# blackfin_f_power.net
KiCad netlist of a schematic drawn in Altium Designer
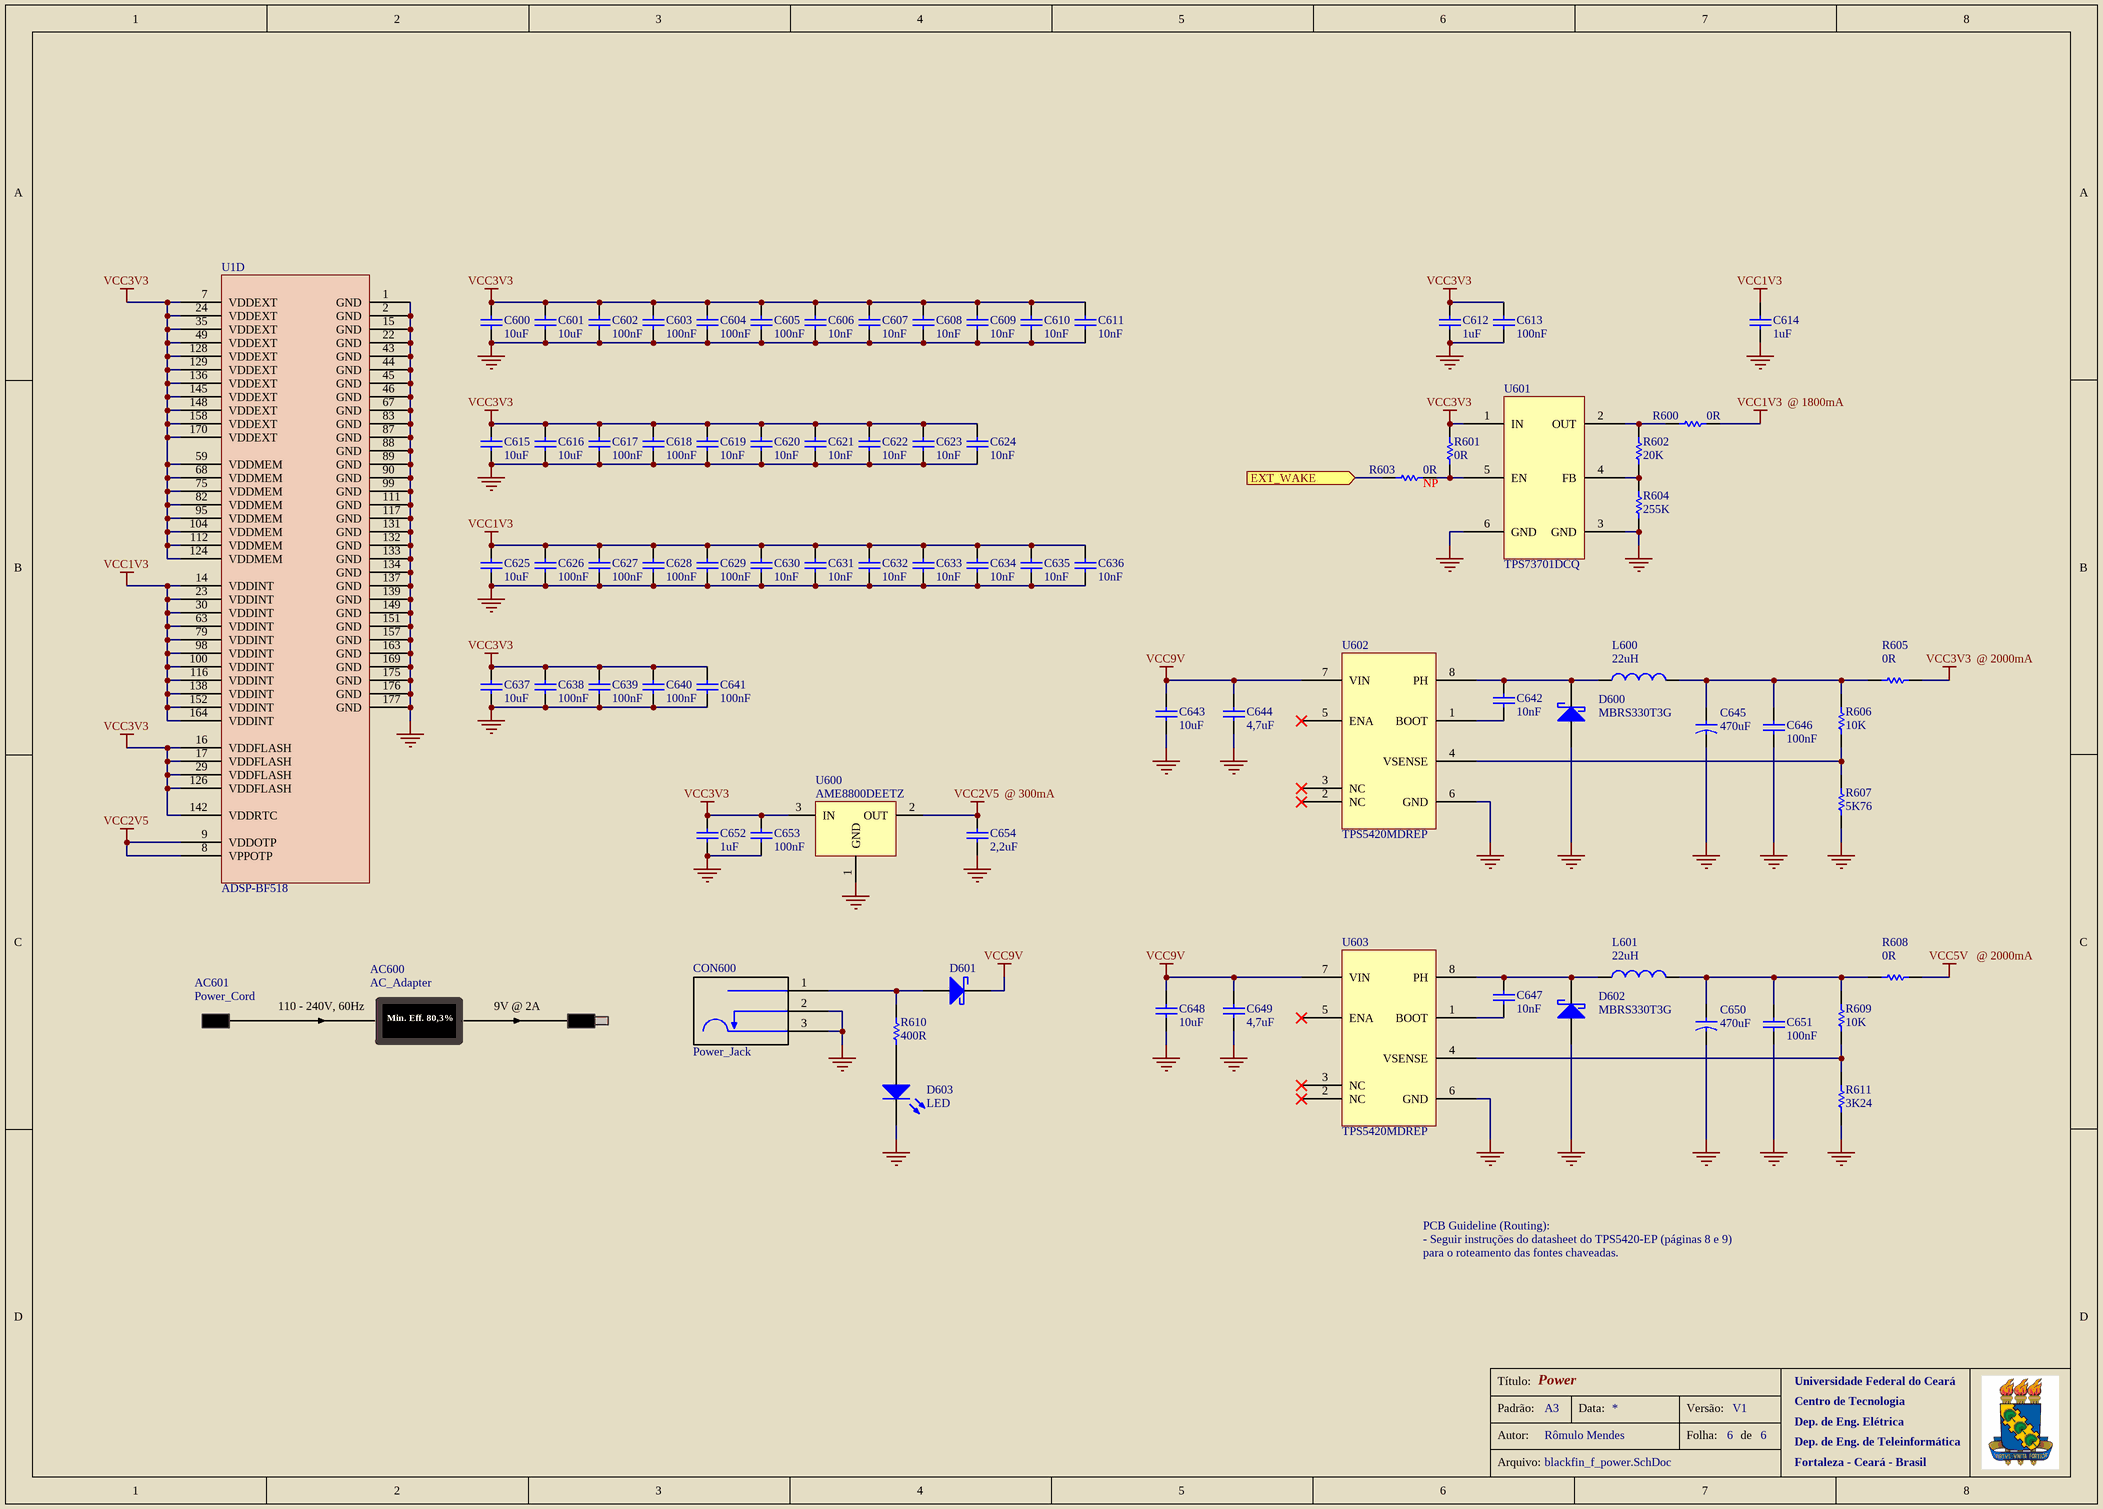
[diagram p0: blackfin_f_power.SchDoc]

(export (version "E")
  (design (tool "Eeschema 10.0.6"))
  (components
    (comp (ref "AC600")
      (value "AC_Adapter")
      (fields
        (field (name "EVENDORPART#") "552-PSA-A18U-090")
        (field (name "PART#") "PSAA18U-090-R")
        (field (name "MANUFACTURER") "Phihong")
      )
      (libsource (lib "blackfin_schlib") (part "AC_Adapter"))
    )
    (comp (ref "AC601")
      (value "Power_Cord")
      (fields
        (field (name "EVENDORPART#") "693-6009.1315")
        (field (name "PART#") "6009.1315")
        (field (name "MANUFACTURER") "Schurter")
      )
      (libsource (lib "blackfin_schlib") (part "Power_Cord"))
    )
    (comp (ref "C600")
      (value "10uF")
      (footprint "blackfin_pcblib:C_0805")
      (fields
        (field (name "EVENDORPART#") "810-C2012Y5V1C106Z")
        (field (name "MANUFACTURER") "TDK")
        (field (name "PART#") "C2012Y5V1C106Z")
      )
      (libsource (lib "blackfin_schlib") (part "Capacitor"))
    )
    (comp (ref "C601")
      (value "10uF")
      (footprint "blackfin_pcblib:C_0805")
      (fields
        (field (name "EVENDORPART#") "810-C2012Y5V1C106Z")
        (field (name "MANUFACTURER") "TDK")
        (field (name "PART#") "C2012Y5V1C106Z")
      )
      (libsource (lib "blackfin_schlib") (part "Capacitor"))
    )
    (comp (ref "C602")
      (value "100nF")
      (footprint "blackfin_pcblib:C_0603")
      (fields
        (field (name "EVENDORPART#") "81-GRM188R71E104KA01")
        (field (name "MANUFACTURER") "Murata")
        (field (name "PART#") "GRM188R71E104KA01J")
      )
      (libsource (lib "blackfin_schlib") (part "Capacitor"))
    )
    (comp (ref "C603")
      (value "100nF")
      (footprint "blackfin_pcblib:C_0603")
      (fields
        (field (name "EVENDORPART#") "81-GRM188R71E104KA01")
        (field (name "MANUFACTURER") "Murata")
        (field (name "PART#") "GRM188R71E104KA01J")
      )
      (libsource (lib "blackfin_schlib") (part "Capacitor"))
    )
    (comp (ref "C604")
      (value "100nF")
      (footprint "blackfin_pcblib:C_0603")
      (fields
        (field (name "EVENDORPART#") "81-GRM188R71E104KA01")
        (field (name "MANUFACTURER") "Murata")
        (field (name "PART#") "GRM188R71E104KA01J")
      )
      (libsource (lib "blackfin_schlib") (part "Capacitor"))
    )
    (comp (ref "C605")
      (value "100nF")
      (footprint "blackfin_pcblib:C_0603")
      (fields
        (field (name "EVENDORPART#") "81-GRM188R71E104KA01")
        (field (name "MANUFACTURER") "Murata")
        (field (name "PART#") "GRM188R71E104KA01J")
      )
      (libsource (lib "blackfin_schlib") (part "Capacitor"))
    )
    (comp (ref "C606")
      (value "10nF")
      (footprint "blackfin_pcblib:C_0603")
      (fields
        (field (name "EVENDORPART#") "77-VJ0603Y103KXAPBC")
        (field (name "MANUFACTURER") "Vishay/Vitramon")
        (field (name "PART#") "VJ0603Y103KXAPW1BC")
      )
      (libsource (lib "blackfin_schlib") (part "Capacitor"))
    )
    (comp (ref "C607")
      (value "10nF")
      (footprint "blackfin_pcblib:C_0603")
      (fields
        (field (name "EVENDORPART#") "77-VJ0603Y103KXAPBC")
        (field (name "MANUFACTURER") "Vishay/Vitramon")
        (field (name "PART#") "VJ0603Y103KXAPW1BC")
      )
      (libsource (lib "blackfin_schlib") (part "Capacitor"))
    )
    (comp (ref "C608")
      (value "10nF")
      (footprint "blackfin_pcblib:C_0603")
      (fields
        (field (name "EVENDORPART#") "77-VJ0603Y103KXAPBC")
        (field (name "MANUFACTURER") "Vishay/Vitramon")
        (field (name "PART#") "VJ0603Y103KXAPW1BC")
      )
      (libsource (lib "blackfin_schlib") (part "Capacitor"))
    )
    (comp (ref "C609")
      (value "10nF")
      (footprint "blackfin_pcblib:C_0603")
      (fields
        (field (name "EVENDORPART#") "77-VJ0603Y103KXAPBC")
        (field (name "MANUFACTURER") "Vishay/Vitramon")
        (field (name "PART#") "VJ0603Y103KXAPW1BC")
      )
      (libsource (lib "blackfin_schlib") (part "Capacitor"))
    )
    (comp (ref "C610")
      (value "10nF")
      (footprint "blackfin_pcblib:C_0603")
      (fields
        (field (name "EVENDORPART#") "77-VJ0603Y103KXAPBC")
        (field (name "MANUFACTURER") "Vishay/Vitramon")
        (field (name "PART#") "VJ0603Y103KXAPW1BC")
      )
      (libsource (lib "blackfin_schlib") (part "Capacitor"))
    )
    (comp (ref "C611")
      (value "10nF")
      (footprint "blackfin_pcblib:C_0603")
      (fields
        (field (name "EVENDORPART#") "77-VJ0603Y103KXAPBC")
        (field (name "MANUFACTURER") "Vishay/Vitramon")
        (field (name "PART#") "VJ0603Y103KXAPW1BC")
      )
      (libsource (lib "blackfin_schlib") (part "Capacitor"))
    )
    (comp (ref "C612")
      (value "1uF")
      (footprint "blackfin_pcblib:C_0603")
      (fields
        (field (name "EVENDORPART#") "81-GRM188F51E105ZA12")
        (field (name "MANUFACTURER") "Murata")
        (field (name "PART#") "GRM188F51E105ZA12D")
      )
      (libsource (lib "blackfin_schlib") (part "Capacitor"))
    )
    (comp (ref "C613")
      (value "100nF")
      (footprint "blackfin_pcblib:C_0603")
      (fields
        (field (name "EVENDORPART#") "81-GRM188R71E104KA01")
        (field (name "MANUFACTURER") "Murata")
        (field (name "PART#") "GRM188R71E104KA01J")
      )
      (libsource (lib "blackfin_schlib") (part "Capacitor"))
    )
    (comp (ref "C614")
      (value "1uF")
      (footprint "blackfin_pcblib:C_0603")
      (fields
        (field (name "EVENDORPART#") "81-GRM188F51E105ZA12")
        (field (name "MANUFACTURER") "Murata")
        (field (name "PART#") "GRM188F51E105ZA12D")
      )
      (libsource (lib "blackfin_schlib") (part "Capacitor"))
    )
    (comp (ref "C615")
      (value "10uF")
      (footprint "blackfin_pcblib:C_0805")
      (fields
        (field (name "EVENDORPART#") "810-C2012Y5V1C106Z")
        (field (name "MANUFACTURER") "TDK")
        (field (name "PART#") "C2012Y5V1C106Z")
      )
      (libsource (lib "blackfin_schlib") (part "Capacitor"))
    )
    (comp (ref "C616")
      (value "10uF")
      (footprint "blackfin_pcblib:C_0805")
      (fields
        (field (name "EVENDORPART#") "810-C2012Y5V1C106Z")
        (field (name "MANUFACTURER") "TDK")
        (field (name "PART#") "C2012Y5V1C106Z")
      )
      (libsource (lib "blackfin_schlib") (part "Capacitor"))
    )
    (comp (ref "C617")
      (value "100nF")
      (footprint "blackfin_pcblib:C_0603")
      (fields
        (field (name "EVENDORPART#") "81-GRM188R71E104KA01")
        (field (name "MANUFACTURER") "Murata")
        (field (name "PART#") "GRM188R71E104KA01J")
      )
      (libsource (lib "blackfin_schlib") (part "Capacitor"))
    )
    (comp (ref "C618")
      (value "100nF")
      (footprint "blackfin_pcblib:C_0603")
      (fields
        (field (name "EVENDORPART#") "81-GRM188R71E104KA01")
        (field (name "MANUFACTURER") "Murata")
        (field (name "PART#") "GRM188R71E104KA01J")
      )
      (libsource (lib "blackfin_schlib") (part "Capacitor"))
    )
    (comp (ref "C619")
      (value "10nF")
      (footprint "blackfin_pcblib:C_0603")
      (fields
        (field (name "EVENDORPART#") "77-VJ0603Y103KXAPBC")
        (field (name "MANUFACTURER") "Vishay/Vitramon")
        (field (name "PART#") "VJ0603Y103KXAPW1BC")
      )
      (libsource (lib "blackfin_schlib") (part "Capacitor"))
    )
    (comp (ref "C620")
      (value "10nF")
      (footprint "blackfin_pcblib:C_0603")
      (fields
        (field (name "EVENDORPART#") "77-VJ0603Y103KXAPBC")
        (field (name "MANUFACTURER") "Vishay/Vitramon")
        (field (name "PART#") "VJ0603Y103KXAPW1BC")
      )
      (libsource (lib "blackfin_schlib") (part "Capacitor"))
    )
    (comp (ref "C621")
      (value "10nF")
      (footprint "blackfin_pcblib:C_0603")
      (fields
        (field (name "EVENDORPART#") "77-VJ0603Y103KXAPBC")
        (field (name "MANUFACTURER") "Vishay/Vitramon")
        (field (name "PART#") "VJ0603Y103KXAPW1BC")
      )
      (libsource (lib "blackfin_schlib") (part "Capacitor"))
    )
    (comp (ref "C622")
      (value "10nF")
      (footprint "blackfin_pcblib:C_0603")
      (fields
        (field (name "EVENDORPART#") "77-VJ0603Y103KXAPBC")
        (field (name "MANUFACTURER") "Vishay/Vitramon")
        (field (name "PART#") "VJ0603Y103KXAPW1BC")
      )
      (libsource (lib "blackfin_schlib") (part "Capacitor"))
    )
    (comp (ref "C623")
      (value "10nF")
      (footprint "blackfin_pcblib:C_0603")
      (fields
        (field (name "EVENDORPART#") "77-VJ0603Y103KXAPBC")
        (field (name "MANUFACTURER") "Vishay/Vitramon")
        (field (name "PART#") "VJ0603Y103KXAPW1BC")
      )
      (libsource (lib "blackfin_schlib") (part "Capacitor"))
    )
    (comp (ref "C624")
      (value "10nF")
      (footprint "blackfin_pcblib:C_0603")
      (fields
        (field (name "EVENDORPART#") "77-VJ0603Y103KXAPBC")
        (field (name "MANUFACTURER") "Vishay/Vitramon")
        (field (name "PART#") "VJ0603Y103KXAPW1BC")
      )
      (libsource (lib "blackfin_schlib") (part "Capacitor"))
    )
    (comp (ref "C625")
      (value "10uF")
      (footprint "blackfin_pcblib:C_0805")
      (fields
        (field (name "EVENDORPART#") "810-C2012Y5V1C106Z")
        (field (name "MANUFACTURER") "TDK")
        (field (name "PART#") "C2012Y5V1C106Z")
      )
      (libsource (lib "blackfin_schlib") (part "Capacitor"))
    )
    (comp (ref "C626")
      (value "100nF")
      (footprint "blackfin_pcblib:C_0603")
      (fields
        (field (name "EVENDORPART#") "81-GRM188R71E104KA01")
        (field (name "MANUFACTURER") "Murata")
        (field (name "PART#") "GRM188R71E104KA01J")
      )
      (libsource (lib "blackfin_schlib") (part "Capacitor"))
    )
    (comp (ref "C627")
      (value "100nF")
      (footprint "blackfin_pcblib:C_0603")
      (fields
        (field (name "EVENDORPART#") "81-GRM188R71E104KA01")
        (field (name "MANUFACTURER") "Murata")
        (field (name "PART#") "GRM188R71E104KA01J")
      )
      (libsource (lib "blackfin_schlib") (part "Capacitor"))
    )
    (comp (ref "C628")
      (value "100nF")
      (footprint "blackfin_pcblib:C_0603")
      (fields
        (field (name "EVENDORPART#") "81-GRM188R71E104KA01")
        (field (name "MANUFACTURER") "Murata")
        (field (name "PART#") "GRM188R71E104KA01J")
      )
      (libsource (lib "blackfin_schlib") (part "Capacitor"))
    )
    (comp (ref "C629")
      (value "100nF")
      (footprint "blackfin_pcblib:C_0603")
      (fields
        (field (name "EVENDORPART#") "81-GRM188R71E104KA01")
        (field (name "MANUFACTURER") "Murata")
        (field (name "PART#") "GRM188R71E104KA01J")
      )
      (libsource (lib "blackfin_schlib") (part "Capacitor"))
    )
    (comp (ref "C630")
      (value "10nF")
      (footprint "blackfin_pcblib:C_0603")
      (fields
        (field (name "EVENDORPART#") "77-VJ0603Y103KXAPBC")
        (field (name "MANUFACTURER") "Vishay/Vitramon")
        (field (name "PART#") "VJ0603Y103KXAPW1BC")
      )
      (libsource (lib "blackfin_schlib") (part "Capacitor"))
    )
    (comp (ref "C631")
      (value "10nF")
      (footprint "blackfin_pcblib:C_0603")
      (fields
        (field (name "EVENDORPART#") "77-VJ0603Y103KXAPBC")
        (field (name "MANUFACTURER") "Vishay/Vitramon")
        (field (name "PART#") "VJ0603Y103KXAPW1BC")
      )
      (libsource (lib "blackfin_schlib") (part "Capacitor"))
    )
    (comp (ref "C632")
      (value "10nF")
      (footprint "blackfin_pcblib:C_0603")
      (fields
        (field (name "EVENDORPART#") "77-VJ0603Y103KXAPBC")
        (field (name "MANUFACTURER") "Vishay/Vitramon")
        (field (name "PART#") "VJ0603Y103KXAPW1BC")
      )
      (libsource (lib "blackfin_schlib") (part "Capacitor"))
    )
    (comp (ref "C633")
      (value "10nF")
      (footprint "blackfin_pcblib:C_0603")
      (fields
        (field (name "EVENDORPART#") "77-VJ0603Y103KXAPBC")
        (field (name "MANUFACTURER") "Vishay/Vitramon")
        (field (name "PART#") "VJ0603Y103KXAPW1BC")
      )
      (libsource (lib "blackfin_schlib") (part "Capacitor"))
    )
    (comp (ref "C634")
      (value "10nF")
      (footprint "blackfin_pcblib:C_0603")
      (fields
        (field (name "EVENDORPART#") "77-VJ0603Y103KXAPBC")
        (field (name "MANUFACTURER") "Vishay/Vitramon")
        (field (name "PART#") "VJ0603Y103KXAPW1BC")
      )
      (libsource (lib "blackfin_schlib") (part "Capacitor"))
    )
    (comp (ref "C635")
      (value "10nF")
      (footprint "blackfin_pcblib:C_0603")
      (fields
        (field (name "EVENDORPART#") "77-VJ0603Y103KXAPBC")
        (field (name "MANUFACTURER") "Vishay/Vitramon")
        (field (name "PART#") "VJ0603Y103KXAPW1BC")
      )
      (libsource (lib "blackfin_schlib") (part "Capacitor"))
    )
    (comp (ref "C636")
      (value "10nF")
      (footprint "blackfin_pcblib:C_0603")
      (fields
        (field (name "EVENDORPART#") "77-VJ0603Y103KXAPBC")
        (field (name "MANUFACTURER") "Vishay/Vitramon")
        (field (name "PART#") "VJ0603Y103KXAPW1BC")
      )
      (libsource (lib "blackfin_schlib") (part "Capacitor"))
    )
    (comp (ref "C637")
      (value "10uF")
      (footprint "blackfin_pcblib:C_0805")
      (fields
        (field (name "EVENDORPART#") "810-C2012Y5V1C106Z")
        (field (name "MANUFACTURER") "TDK")
        (field (name "PART#") "C2012Y5V1C106Z")
      )
      (libsource (lib "blackfin_schlib") (part "Capacitor"))
    )
    (comp (ref "C638")
      (value "100nF")
      (footprint "blackfin_pcblib:C_0603")
      (fields
        (field (name "EVENDORPART#") "81-GRM188R71E104KA01")
        (field (name "MANUFACTURER") "Murata")
        (field (name "PART#") "GRM188R71E104KA01J")
      )
      (libsource (lib "blackfin_schlib") (part "Capacitor"))
    )
    (comp (ref "C639")
      (value "100nF")
      (footprint "blackfin_pcblib:C_0603")
      (fields
        (field (name "EVENDORPART#") "81-GRM188R71E104KA01")
        (field (name "MANUFACTURER") "Murata")
        (field (name "PART#") "GRM188R71E104KA01J")
      )
      (libsource (lib "blackfin_schlib") (part "Capacitor"))
    )
    (comp (ref "C640")
      (value "100nF")
      (footprint "blackfin_pcblib:C_0603")
      (fields
        (field (name "EVENDORPART#") "81-GRM188R71E104KA01")
        (field (name "MANUFACTURER") "Murata")
        (field (name "PART#") "GRM188R71E104KA01J")
      )
      (libsource (lib "blackfin_schlib") (part "Capacitor"))
    )
    (comp (ref "C641")
      (value "100nF")
      (footprint "blackfin_pcblib:C_0603")
      (fields
        (field (name "EVENDORPART#") "81-GRM188R71E104KA01")
        (field (name "MANUFACTURER") "Murata")
        (field (name "PART#") "GRM188R71E104KA01J")
      )
      (libsource (lib "blackfin_schlib") (part "Capacitor"))
    )
    (comp (ref "C642")
      (value "10nF")
      (footprint "blackfin_pcblib:C_0805")
      (fields
        (field (name "EVENDORPART#") "81-GRM216R71H103JA1D")
        (field (name "MANUFACTURER") "Murata")
        (field (name "PART#") "GRM216R71H103JA01D")
      )
      (libsource (lib "blackfin_schlib") (part "Capacitor"))
    )
    (comp (ref "C643")
      (value "10uF")
      (footprint "blackfin_pcblib:C_0805")
      (fields
        (field (name "EVENDORPART#") "810-C2012X5R1C106M")
        (field (name "MANUFACTURER") "TDK")
        (field (name "PART#") "C2012X5R1C106M")
      )
      (libsource (lib "blackfin_schlib") (part "Capacitor"))
    )
    (comp (ref "C644")
      (value "4,7uF")
      (footprint "blackfin_pcblib:C_0805")
      (fields
        (field (name "EVENDORPART#") "81-GRM21BR61C475KA8L")
        (field (name "MANUFACTURER") "Murata")
        (field (name "PART#") "GRM21BR61C475KA88L")
      )
      (libsource (lib "blackfin_schlib") (part "Capacitor"))
    )
    (comp (ref "C645")
      (value "470uF")
      (footprint "blackfin_pcblib:C_Case_Y")
      (fields
        (field (name "EVENDORPART#") "80-T520Y477M6ATE15")
        (field (name "PART#") "T520Y477M006ATE015")
        (field (name "MANUFACTURER") "Kemet")
      )
      (libsource (lib "blackfin_schlib") (part "Capacitor_Pol"))
    )
    (comp (ref "C646")
      (value "100nF")
      (footprint "blackfin_pcblib:C_0603")
      (fields
        (field (name "EVENDORPART#") "81-GRM188R71E104KA01")
        (field (name "MANUFACTURER") "Murata")
        (field (name "PART#") "GRM188R71E104KA01J")
      )
      (libsource (lib "blackfin_schlib") (part "Capacitor"))
    )
    (comp (ref "C647")
      (value "10nF")
      (footprint "blackfin_pcblib:C_0805")
      (fields
        (field (name "EVENDORPART#") "81-GRM216R71H103JA1D")
        (field (name "MANUFACTURER") "Murata")
        (field (name "PART#") "GRM216R71H103JA01D")
      )
      (libsource (lib "blackfin_schlib") (part "Capacitor"))
    )
    (comp (ref "C648")
      (value "10uF")
      (footprint "blackfin_pcblib:C_0805")
      (fields
        (field (name "EVENDORPART#") "810-C2012X5R1C106M")
        (field (name "MANUFACTURER") "TDK")
        (field (name "PART#") "C2012X5R1C106M")
      )
      (libsource (lib "blackfin_schlib") (part "Capacitor"))
    )
    (comp (ref "C649")
      (value "4,7uF")
      (footprint "blackfin_pcblib:C_0805")
      (fields
        (field (name "EVENDORPART#") "81-GRM21BR61C475KA8L")
        (field (name "MANUFACTURER") "Murata")
        (field (name "PART#") "GRM21BR61C475KA88L")
      )
      (libsource (lib "blackfin_schlib") (part "Capacitor"))
    )
    (comp (ref "C650")
      (value "470uF")
      (footprint "blackfin_pcblib:C_Case_Y")
      (fields
        (field (name "EVENDORPART#") "80-T520Y477M6ATE15")
        (field (name "PART#") "T520Y477M006ATE015")
        (field (name "MANUFACTURER") "Kemet")
      )
      (libsource (lib "blackfin_schlib") (part "Capacitor_Pol"))
    )
    (comp (ref "C651")
      (value "100nF")
      (footprint "blackfin_pcblib:C_0603")
      (fields
        (field (name "EVENDORPART#") "81-GRM188R71E104KA01")
        (field (name "MANUFACTURER") "Murata")
        (field (name "PART#") "GRM188R71E104KA01J")
      )
      (libsource (lib "blackfin_schlib") (part "Capacitor"))
    )
    (comp (ref "C652")
      (value "1uF")
      (footprint "blackfin_pcblib:C_0603")
      (fields
        (field (name "EVENDORPART#") "81-GRM188F51E105ZA12")
        (field (name "MANUFACTURER") "Murata")
        (field (name "PART#") "GRM188F51E105ZA12D")
      )
      (libsource (lib "blackfin_schlib") (part "Capacitor"))
    )
    (comp (ref "C653")
      (value "100nF")
      (footprint "blackfin_pcblib:C_0603")
      (fields
        (field (name "EVENDORPART#") "81-GRM188R71E104KA01")
        (field (name "MANUFACTURER") "Murata")
        (field (name "PART#") "GRM188R71E104KA01J")
      )
      (libsource (lib "blackfin_schlib") (part "Capacitor"))
    )
    (comp (ref "C654")
      (value "2,2uF")
      (footprint "blackfin_pcblib:C_0603")
      (fields
        (field (name "EVENDORPART#") "81-GRM188F51A225ZE01")
        (field (name "MANUFACTURER") "Murata")
        (field (name "PART#") "GRM188F51A225ZE01D")
      )
      (libsource (lib "blackfin_schlib") (part "Capacitor"))
    )
    (comp (ref "CON600")
      (value "Power_Jack")
      (footprint "blackfin_pcblib:Power_Jack")
      (fields (field (name "EVENDORPART#") "163-179PH-EX") (field (name "MANUFACTURER") "Kobiconn"))
      (libsource (lib "blackfin_schlib") (part "Power_Jack"))
    )
    (comp (ref "D600")
      (value "MBRS330T3G")
      (footprint "blackfin_pcblib:Case_430")
      (fields (field (name "EVENDORPART#") "863-MBRS330T3G") (field (name "MANUFACTURER") "ON Semiconductor"))
      (libsource (lib "blackfin_schlib") (part "Schottky_Diode"))
    )
    (comp (ref "D601")
      (value "MBRS330T3G")
      (footprint "blackfin_pcblib:Case_430")
      (fields (field (name "EVENDORPART#") "863-MBRS330T3G") (field (name "MANUFACTURER") "ON Semiconductor"))
      (libsource (lib "blackfin_schlib") (part "Schottky_Diode"))
    )
    (comp (ref "D602")
      (value "MBRS330T3G")
      (footprint "blackfin_pcblib:Case_430")
      (fields (field (name "EVENDORPART#") "863-MBRS330T3G") (field (name "MANUFACTURER") "ON Semiconductor"))
      (libsource (lib "blackfin_schlib") (part "Schottky_Diode"))
    )
    (comp (ref "D603")
      (value "LED")
      (footprint "blackfin_pcblib:LED_0603")
      (description "Red LED")
      (fields (field (name "EVENDORPART#") "638-QTLP600C2TR") (field (name "MANUFACTURER") "Everlight"))
      (libsource (lib "blackfin_schlib") (part "LED"))
    )
    (comp (ref "L600")
      (value "22uH")
      (footprint "blackfin_pcblib:Inductor_22uH")
      (fields
        (field (name "EVENDORPART#") "710-744066220")
        (field (name "MANUFACTURER") "Wurth Electronics")
        (field (name "PART#") "744066220")
      )
      (libsource (lib "blackfin_schlib") (part "Inductor"))
    )
    (comp (ref "L601")
      (value "22uH")
      (footprint "blackfin_pcblib:Inductor_22uH")
      (fields
        (field (name "EVENDORPART#") "710-744066220")
        (field (name "MANUFACTURER") "Wurth Electronics")
        (field (name "PART#") "744066220")
      )
      (libsource (lib "blackfin_schlib") (part "Inductor"))
    )
    (comp (ref "R600")
      (value "0R")
      (footprint "blackfin_pcblib:R_0603")
      (fields
        (field (name "EVENDORPART#") "71-CRCW06030000Z0EB")
        (field (name "PART#") "CRCW06030000Z0EB")
        (field (name "MANUFACTURER") "Vishay/Dale")
      )
      (libsource (lib "blackfin_schlib") (part "Resistor"))
    )
    (comp (ref "R601")
      (value "0R")
      (footprint "blackfin_pcblib:R_0603")
      (fields
        (field (name "EVENDORPART#") "71-CRCW06030000Z0EB")
        (field (name "PART#") "CRCW06030000Z0EB")
        (field (name "MANUFACTURER") "Vishay/Dale")
      )
      (libsource (lib "blackfin_schlib") (part "Resistor"))
    )
    (comp (ref "R602")
      (value "20K")
      (footprint "blackfin_pcblib:R_0603")
      (fields
        (field (name "EVENDORPART#") "71-CRCW0603J-20K-E3")
        (field (name "PART#") "CRCW060320K0JNEA")
        (field (name "MANUFACTURER") "Vishay/Dale")
      )
      (libsource (lib "blackfin_schlib") (part "Resistor"))
    )
    (comp (ref "R603")
      (value "0R")
      (footprint "blackfin_pcblib:R_0603")
      (fields
        (field (name "EVENDORPART#") "71-CRCW06030000Z0EB")
        (field (name "PART#") "CRCW06030000Z0EB")
        (field (name "MANUFACTURER") "Vishay/Dale")
      )
      (libsource (lib "blackfin_schlib") (part "Resistor"))
    )
    (comp (ref "R604")
      (value "255K")
      (footprint "blackfin_pcblib:R_0603")
      (fields
        (field (name "EVENDORPART#") "71-CRCW0603-255K-E3")
        (field (name "PART#") "CRCW0603255KFKEA")
        (field (name "MANUFACTURER") "Vishay/Dale")
      )
      (libsource (lib "blackfin_schlib") (part "Resistor"))
    )
    (comp (ref "R605")
      (value "0R")
      (footprint "blackfin_pcblib:R_2512")
      (fields
        (field (name "EVENDORPART#") "71-CRCW2512-0-E3")
        (field (name "PART#") "CRCW25120000Z0EG")
        (field (name "MANUFACTURER") "Vishay/Dale")
      )
      (libsource (lib "blackfin_schlib") (part "Resistor"))
    )
    (comp (ref "R606")
      (value "10K")
      (footprint "blackfin_pcblib:R_0603")
      (fields
        (field (name "EVENDORPART#") "71-CRCW0603-10K-E3")
        (field (name "PART#") "CRCW060310K0FKEA")
        (field (name "MANUFACTURER") "Vishay/Dale")
      )
      (libsource (lib "blackfin_schlib") (part "Resistor"))
    )
    (comp (ref "R607")
      (value "5K76")
      (footprint "blackfin_pcblib:R_0603")
      (fields
        (field (name "EVENDORPART#") "660-RK73H1JTTDD5761F")
        (field (name "PART#") "RK73H1JTTDD5761F")
        (field (name "MANUFACTURER") "KOA Speer")
      )
      (libsource (lib "blackfin_schlib") (part "Resistor"))
    )
    (comp (ref "R608")
      (value "0R")
      (footprint "blackfin_pcblib:R_2512")
      (fields
        (field (name "EVENDORPART#") "71-CRCW2512-0-E3")
        (field (name "PART#") "CRCW25120000Z0EG")
        (field (name "MANUFACTURER") "Vishay/Dale")
      )
      (libsource (lib "blackfin_schlib") (part "Resistor"))
    )
    (comp (ref "R609")
      (value "10K")
      (footprint "blackfin_pcblib:R_0603")
      (fields
        (field (name "EVENDORPART#") "71-CRCW0603-10K-E3")
        (field (name "PART#") "CRCW060310K0FKEA")
        (field (name "MANUFACTURER") "Vishay/Dale")
      )
      (libsource (lib "blackfin_schlib") (part "Resistor"))
    )
    (comp (ref "R610")
      (value "400R")
      (footprint "blackfin_pcblib:R_1206")
      (fields
        (field (name "EVENDORPART#") "71-CRCW1206390RJNEB")
        (field (name "PART#") "CRCW1206390RJNEB")
        (field (name "MANUFACTURER") "Vishay/Dale")
      )
      (libsource (lib "blackfin_schlib") (part "Resistor"))
    )
    (comp (ref "R611")
      (value "3K24")
      (footprint "blackfin_pcblib:R_0603")
      (fields
        (field (name "EVENDORPART#") "71-CRCW0603-3.24K-E3")
        (field (name "PART#") "CRCW06033K24FKEA")
        (field (name "MANUFACTURER") "Vishay/Dale")
      )
      (libsource (lib "blackfin_schlib") (part "Resistor"))
    )
    (comp (ref "U1")
      (value "ADSP-BF518")
      (footprint "blackfin_pcblib:LQFP-176")
      (fields (field (name "EVENDORPART#") "ADSP-BF518BSWZ-4") (field (name "MANUFACTURER") "Analog Devices"))
      (libsource (lib "blackfin_schlib") (part "ADSP-BF518"))
    )
    (comp (ref "U600")
      (value "AME8800DEETZ")
      (footprint "blackfin_pcblib:SOT-23")
      (fields (field (name "EVENDORPART#") "827-AME8800DEETZ") (field (name "MANUFACTURER") "AME"))
      (libsource (lib "blackfin_schlib") (part "AME8800DEETZ"))
    )
    (comp (ref "U601")
      (value "TPS73701DCQ")
      (footprint "blackfin_pcblib:SOT-223")
      (fields
        (field (name "EVENDORPART#") "595-TPS73701DCQ")
        (field (name "MANUFACTURER") "Texas Instruments")
      )
      (libsource (lib "blackfin_schlib") (part "TPS73701DCQ"))
    )
    (comp (ref "U602")
      (value "TPS5420MDREP")
      (footprint "blackfin_pcblib:SOIC-8 (TPS5420MDREP)")
      (fields
        (field (name "EVENDORPART#") "595-TPS5420MDREP")
        (field (name "MANUFACTURER") "Texas Instruments")
      )
      (libsource (lib "blackfin_schlib") (part "TPS5420MDREP"))
    )
    (comp (ref "U603")
      (value "TPS5420MDREP")
      (footprint "blackfin_pcblib:SOIC-8 (TPS5420MDREP)")
      (fields
        (field (name "EVENDORPART#") "595-TPS5420MDREP")
        (field (name "MANUFACTURER") "Texas Instruments")
      )
      (libsource (lib "blackfin_schlib") (part "TPS5420MDREP"))
    )
  )
  (nets
    (net (code "1") (name "/EXT_WAKE") (class "Default")
      (node (ref "R603") (pin "1") (pinfunction "1_1") (pintype "passive"))
    )
    (net (code "2") (name "GND") (class "Default")
      (node (ref "C600") (pin "1") (pinfunction "1_1") (pintype "passive"))
      (node (ref "C601") (pin "1") (pinfunction "1_1") (pintype "passive"))
      (node (ref "C602") (pin "1") (pinfunction "1_1") (pintype "passive"))
      (node (ref "C603") (pin "1") (pinfunction "1_1") (pintype "passive"))
      (node (ref "C604") (pin "1") (pinfunction "1_1") (pintype "passive"))
      (node (ref "C605") (pin "1") (pinfunction "1_1") (pintype "passive"))
      (node (ref "C606") (pin "1") (pinfunction "1_1") (pintype "passive"))
      (node (ref "C607") (pin "1") (pinfunction "1_1") (pintype "passive"))
      (node (ref "C608") (pin "1") (pinfunction "1_1") (pintype "passive"))
      (node (ref "C609") (pin "1") (pinfunction "1_1") (pintype "passive"))
      (node (ref "C610") (pin "1") (pinfunction "1_1") (pintype "passive"))
      (node (ref "C611") (pin "1") (pinfunction "1_1") (pintype "passive"))
      (node (ref "C612") (pin "1") (pinfunction "1_1") (pintype "passive"))
      (node (ref "C613") (pin "1") (pinfunction "1_1") (pintype "passive"))
      (node (ref "C614") (pin "1") (pinfunction "1_1") (pintype "passive"))
      (node (ref "C615") (pin "1") (pinfunction "1_1") (pintype "passive"))
      (node (ref "C616") (pin "1") (pinfunction "1_1") (pintype "passive"))
      (node (ref "C617") (pin "1") (pinfunction "1_1") (pintype "passive"))
      (node (ref "C618") (pin "1") (pinfunction "1_1") (pintype "passive"))
      (node (ref "C619") (pin "1") (pinfunction "1_1") (pintype "passive"))
      (node (ref "C620") (pin "1") (pinfunction "1_1") (pintype "passive"))
      (node (ref "C621") (pin "1") (pinfunction "1_1") (pintype "passive"))
      (node (ref "C622") (pin "1") (pinfunction "1_1") (pintype "passive"))
      (node (ref "C623") (pin "1") (pinfunction "1_1") (pintype "passive"))
      (node (ref "C624") (pin "1") (pinfunction "1_1") (pintype "passive"))
      (node (ref "C625") (pin "1") (pinfunction "1_1") (pintype "passive"))
      (node (ref "C626") (pin "1") (pinfunction "1_1") (pintype "passive"))
      (node (ref "C627") (pin "1") (pinfunction "1_1") (pintype "passive"))
      (node (ref "C628") (pin "1") (pinfunction "1_1") (pintype "passive"))
      (node (ref "C629") (pin "1") (pinfunction "1_1") (pintype "passive"))
      (node (ref "C630") (pin "1") (pinfunction "1_1") (pintype "passive"))
      (node (ref "C631") (pin "1") (pinfunction "1_1") (pintype "passive"))
      (node (ref "C632") (pin "1") (pinfunction "1_1") (pintype "passive"))
      (node (ref "C633") (pin "1") (pinfunction "1_1") (pintype "passive"))
      (node (ref "C634") (pin "1") (pinfunction "1_1") (pintype "passive"))
      (node (ref "C635") (pin "1") (pinfunction "1_1") (pintype "passive"))
      (node (ref "C636") (pin "1") (pinfunction "1_1") (pintype "passive"))
      (node (ref "C637") (pin "1") (pinfunction "1_1") (pintype "passive"))
      (node (ref "C638") (pin "1") (pinfunction "1_1") (pintype "passive"))
      (node (ref "C639") (pin "1") (pinfunction "1_1") (pintype "passive"))
      (node (ref "C640") (pin "1") (pinfunction "1_1") (pintype "passive"))
      (node (ref "C641") (pin "1") (pinfunction "1_1") (pintype "passive"))
      (node (ref "C643") (pin "1") (pinfunction "1_1") (pintype "passive"))
      (node (ref "C644") (pin "1") (pinfunction "1_1") (pintype "passive"))
      (node (ref "C645") (pin "2") (pinfunction "2_2") (pintype "passive"))
      (node (ref "C646") (pin "1") (pinfunction "1_1") (pintype "passive"))
      (node (ref "C648") (pin "1") (pinfunction "1_1") (pintype "passive"))
      (node (ref "C649") (pin "1") (pinfunction "1_1") (pintype "passive"))
      (node (ref "C650") (pin "2") (pinfunction "2_2") (pintype "passive"))
      (node (ref "C651") (pin "1") (pinfunction "1_1") (pintype "passive"))
      (node (ref "C652") (pin "1") (pinfunction "1_1") (pintype "passive"))
      (node (ref "C653") (pin "1") (pinfunction "1_1") (pintype "passive"))
      (node (ref "C654") (pin "1") (pinfunction "1_1") (pintype "passive"))
      (node (ref "CON600") (pin "2") (pinfunction "2_2") (pintype "passive"))
      (node (ref "CON600") (pin "3") (pinfunction "3_3") (pintype "passive"))
      (node (ref "D600") (pin "1") (pinfunction "A_1") (pintype "passive"))
      (node (ref "D602") (pin "1") (pinfunction "A_1") (pintype "passive"))
      (node (ref "D603") (pin "2") (pinfunction "K_2") (pintype "passive"))
      (node (ref "R604") (pin "1") (pinfunction "1_1") (pintype "passive"))
      (node (ref "R607") (pin "1") (pinfunction "1_1") (pintype "passive"))
      (node (ref "R611") (pin "1") (pinfunction "1_1") (pintype "passive"))
      (node (ref "U1") (pin "1") (pinfunction "GND_1") (pintype "passive"))
      (node (ref "U1") (pin "111") (pinfunction "GND_111") (pintype "passive"))
      (node (ref "U1") (pin "117") (pinfunction "GND_117") (pintype "passive"))
      (node (ref "U1") (pin "131") (pinfunction "GND_131") (pintype "passive"))
      (node (ref "U1") (pin "132") (pinfunction "GND_132") (pintype "passive"))
      (node (ref "U1") (pin "133") (pinfunction "GND_133") (pintype "passive"))
      (node (ref "U1") (pin "134") (pinfunction "GND_134") (pintype "passive"))
      (node (ref "U1") (pin "137") (pinfunction "GND_137") (pintype "passive"))
      (node (ref "U1") (pin "139") (pinfunction "GND_139") (pintype "passive"))
      (node (ref "U1") (pin "149") (pinfunction "GND_149") (pintype "passive"))
      (node (ref "U1") (pin "15") (pinfunction "GND_15") (pintype "passive"))
      (node (ref "U1") (pin "151") (pinfunction "GND_151") (pintype "passive"))
      (node (ref "U1") (pin "157") (pinfunction "GND_157") (pintype "passive"))
      (node (ref "U1") (pin "163") (pinfunction "GND_163") (pintype "passive"))
      (node (ref "U1") (pin "169") (pinfunction "GND_169") (pintype "passive"))
      (node (ref "U1") (pin "175") (pinfunction "GND_175") (pintype "passive"))
      (node (ref "U1") (pin "176") (pinfunction "GND_176") (pintype "passive"))
      (node (ref "U1") (pin "177") (pinfunction "GND_177") (pintype "passive"))
      (node (ref "U1") (pin "2") (pinfunction "GND_2") (pintype "passive"))
      (node (ref "U1") (pin "22") (pinfunction "GND_22") (pintype "passive"))
      (node (ref "U1") (pin "43") (pinfunction "GND_43") (pintype "passive"))
      (node (ref "U1") (pin "44") (pinfunction "GND_44") (pintype "passive"))
      (node (ref "U1") (pin "45") (pinfunction "GND_45") (pintype "passive"))
      (node (ref "U1") (pin "46") (pinfunction "GND_46") (pintype "passive"))
      (node (ref "U1") (pin "67") (pinfunction "GND_67") (pintype "passive"))
      (node (ref "U1") (pin "83") (pinfunction "GND_83") (pintype "passive"))
      (node (ref "U1") (pin "87") (pinfunction "GND_87") (pintype "passive"))
      (node (ref "U1") (pin "88") (pinfunction "GND_88") (pintype "passive"))
      (node (ref "U1") (pin "89") (pinfunction "GND_89") (pintype "passive"))
      (node (ref "U1") (pin "90") (pinfunction "GND_90") (pintype "passive"))
      (node (ref "U1") (pin "99") (pinfunction "GND_99") (pintype "passive"))
      (node (ref "U600") (pin "1") (pinfunction "GND_1") (pintype "passive"))
      (node (ref "U601") (pin "3") (pinfunction "GND_3") (pintype "passive"))
      (node (ref "U601") (pin "6") (pinfunction "GND_6") (pintype "passive"))
      (node (ref "U602") (pin "6") (pinfunction "GND_6") (pintype "passive"))
      (node (ref "U603") (pin "6") (pinfunction "GND_6") (pintype "passive"))
    )
    (net (code "3") (name "Net-(C645-Pad1)") (class "Default")
      (node (ref "C645") (pin "1") (pinfunction "1_1") (pintype "passive"))
      (node (ref "C646") (pin "2") (pinfunction "2_2") (pintype "passive"))
      (node (ref "L600") (pin "2") (pinfunction "2_2") (pintype "passive"))
      (node (ref "R605") (pin "1") (pinfunction "1_1") (pintype "passive"))
      (node (ref "R606") (pin "2") (pinfunction "2_2") (pintype "passive"))
    )
    (net (code "4") (name "Net-(C650-Pad1)") (class "Default")
      (node (ref "C650") (pin "1") (pinfunction "1_1") (pintype "passive"))
      (node (ref "C651") (pin "2") (pinfunction "2_2") (pintype "passive"))
      (node (ref "L601") (pin "2") (pinfunction "2_2") (pintype "passive"))
      (node (ref "R608") (pin "1") (pinfunction "1_1") (pintype "passive"))
      (node (ref "R609") (pin "2") (pinfunction "2_2") (pintype "passive"))
    )
    (net (code "5") (name "Net-(D600-K)") (class "Default")
      (node (ref "C642") (pin "2") (pinfunction "2_2") (pintype "passive"))
      (node (ref "D600") (pin "2") (pinfunction "K_2") (pintype "passive"))
      (node (ref "L600") (pin "1") (pinfunction "1_1") (pintype "passive"))
      (node (ref "U602") (pin "8") (pinfunction "PH_8") (pintype "passive"))
    )
    (net (code "6") (name "Net-(D601-A)") (class "Default")
      (node (ref "CON600") (pin "1") (pinfunction "1_1") (pintype "passive"))
      (node (ref "D601") (pin "1") (pinfunction "A_1") (pintype "passive"))
      (node (ref "R610") (pin "2") (pinfunction "2_2") (pintype "passive"))
    )
    (net (code "7") (name "Net-(D602-K)") (class "Default")
      (node (ref "C647") (pin "2") (pinfunction "2_2") (pintype "passive"))
      (node (ref "D602") (pin "2") (pinfunction "K_2") (pintype "passive"))
      (node (ref "L601") (pin "1") (pinfunction "1_1") (pintype "passive"))
      (node (ref "U603") (pin "8") (pinfunction "PH_8") (pintype "passive"))
    )
    (net (code "8") (name "Net-(D603-A)") (class "Default")
      (node (ref "D603") (pin "1") (pinfunction "A_1") (pintype "passive"))
      (node (ref "R610") (pin "1") (pinfunction "1_1") (pintype "passive"))
    )
    (net (code "9") (name "Net-(U601-EN)") (class "Default")
      (node (ref "R601") (pin "1") (pinfunction "1_1") (pintype "passive"))
      (node (ref "R603") (pin "2") (pinfunction "2_2") (pintype "passive"))
      (node (ref "U601") (pin "5") (pinfunction "EN_5") (pintype "passive"))
    )
    (net (code "10") (name "Net-(U601-FB)") (class "Default")
      (node (ref "R602") (pin "1") (pinfunction "1_1") (pintype "passive"))
      (node (ref "R604") (pin "2") (pinfunction "2_2") (pintype "passive"))
      (node (ref "U601") (pin "4") (pinfunction "FB_4") (pintype "passive"))
    )
    (net (code "11") (name "Net-(U601-OUT)") (class "Default")
      (node (ref "R600") (pin "1") (pinfunction "1_1") (pintype "passive"))
      (node (ref "R602") (pin "2") (pinfunction "2_2") (pintype "passive"))
      (node (ref "U601") (pin "2") (pinfunction "OUT_2") (pintype "passive"))
    )
    (net (code "12") (name "Net-(U602-BOOT)") (class "Default")
      (node (ref "C642") (pin "1") (pinfunction "1_1") (pintype "passive"))
      (node (ref "U602") (pin "1") (pinfunction "BOOT_1") (pintype "passive"))
    )
    (net (code "13") (name "Net-(U602-VSENSE)") (class "Default")
      (node (ref "R606") (pin "1") (pinfunction "1_1") (pintype "passive"))
      (node (ref "R607") (pin "2") (pinfunction "2_2") (pintype "passive"))
      (node (ref "U602") (pin "4") (pinfunction "VSENSE_4") (pintype "passive"))
    )
    (net (code "14") (name "Net-(U603-BOOT)") (class "Default")
      (node (ref "C647") (pin "1") (pinfunction "1_1") (pintype "passive"))
      (node (ref "U603") (pin "1") (pinfunction "BOOT_1") (pintype "passive"))
    )
    (net (code "15") (name "Net-(U603-VSENSE)") (class "Default")
      (node (ref "R609") (pin "1") (pinfunction "1_1") (pintype "passive"))
      (node (ref "R611") (pin "2") (pinfunction "2_2") (pintype "passive"))
      (node (ref "U603") (pin "4") (pinfunction "VSENSE_4") (pintype "passive"))
    )
    (net (code "16") (name "VCC1V3") (class "Default")
      (node (ref "C614") (pin "2") (pinfunction "2_2") (pintype "passive"))
      (node (ref "C625") (pin "2") (pinfunction "2_2") (pintype "passive"))
      (node (ref "C626") (pin "2") (pinfunction "2_2") (pintype "passive"))
      (node (ref "C627") (pin "2") (pinfunction "2_2") (pintype "passive"))
      (node (ref "C628") (pin "2") (pinfunction "2_2") (pintype "passive"))
      (node (ref "C629") (pin "2") (pinfunction "2_2") (pintype "passive"))
      (node (ref "C630") (pin "2") (pinfunction "2_2") (pintype "passive"))
      (node (ref "C631") (pin "2") (pinfunction "2_2") (pintype "passive"))
      (node (ref "C632") (pin "2") (pinfunction "2_2") (pintype "passive"))
      (node (ref "C633") (pin "2") (pinfunction "2_2") (pintype "passive"))
      (node (ref "C634") (pin "2") (pinfunction "2_2") (pintype "passive"))
      (node (ref "C635") (pin "2") (pinfunction "2_2") (pintype "passive"))
      (node (ref "C636") (pin "2") (pinfunction "2_2") (pintype "passive"))
      (node (ref "R600") (pin "2") (pinfunction "2_2") (pintype "passive"))
      (node (ref "U1") (pin "100") (pinfunction "VDDINT_100") (pintype "passive"))
      (node (ref "U1") (pin "116") (pinfunction "VDDINT_116") (pintype "passive"))
      (node (ref "U1") (pin "138") (pinfunction "VDDINT_138") (pintype "passive"))
      (node (ref "U1") (pin "14") (pinfunction "VDDINT_14") (pintype "passive"))
      (node (ref "U1") (pin "152") (pinfunction "VDDINT_152") (pintype "passive"))
      (node (ref "U1") (pin "164") (pinfunction "VDDINT_164") (pintype "passive"))
      (node (ref "U1") (pin "23") (pinfunction "VDDINT_23") (pintype "passive"))
      (node (ref "U1") (pin "30") (pinfunction "VDDINT_30") (pintype "passive"))
      (node (ref "U1") (pin "63") (pinfunction "VDDINT_63") (pintype "passive"))
      (node (ref "U1") (pin "79") (pinfunction "VDDINT_79") (pintype "passive"))
      (node (ref "U1") (pin "98") (pinfunction "VDDINT_98") (pintype "passive"))
    )
    (net (code "17") (name "VCC2V5") (class "Default")
      (node (ref "C654") (pin "2") (pinfunction "2_2") (pintype "passive"))
      (node (ref "U1") (pin "8") (pinfunction "VPPOTP_8") (pintype "passive"))
      (node (ref "U1") (pin "9") (pinfunction "VDDOTP_9") (pintype "passive"))
      (node (ref "U600") (pin "2") (pinfunction "OUT_2") (pintype "passive"))
    )
    (net (code "18") (name "VCC3V3") (class "Default")
      (node (ref "C600") (pin "2") (pinfunction "2_2") (pintype "passive"))
      (node (ref "C601") (pin "2") (pinfunction "2_2") (pintype "passive"))
      (node (ref "C602") (pin "2") (pinfunction "2_2") (pintype "passive"))
      (node (ref "C603") (pin "2") (pinfunction "2_2") (pintype "passive"))
      (node (ref "C604") (pin "2") (pinfunction "2_2") (pintype "passive"))
      (node (ref "C605") (pin "2") (pinfunction "2_2") (pintype "passive"))
      (node (ref "C606") (pin "2") (pinfunction "2_2") (pintype "passive"))
      (node (ref "C607") (pin "2") (pinfunction "2_2") (pintype "passive"))
      (node (ref "C608") (pin "2") (pinfunction "2_2") (pintype "passive"))
      (node (ref "C609") (pin "2") (pinfunction "2_2") (pintype "passive"))
      (node (ref "C610") (pin "2") (pinfunction "2_2") (pintype "passive"))
      (node (ref "C611") (pin "2") (pinfunction "2_2") (pintype "passive"))
      (node (ref "C612") (pin "2") (pinfunction "2_2") (pintype "passive"))
      (node (ref "C613") (pin "2") (pinfunction "2_2") (pintype "passive"))
      (node (ref "C615") (pin "2") (pinfunction "2_2") (pintype "passive"))
      (node (ref "C616") (pin "2") (pinfunction "2_2") (pintype "passive"))
      (node (ref "C617") (pin "2") (pinfunction "2_2") (pintype "passive"))
      (node (ref "C618") (pin "2") (pinfunction "2_2") (pintype "passive"))
      (node (ref "C619") (pin "2") (pinfunction "2_2") (pintype "passive"))
      (node (ref "C620") (pin "2") (pinfunction "2_2") (pintype "passive"))
      (node (ref "C621") (pin "2") (pinfunction "2_2") (pintype "passive"))
      (node (ref "C622") (pin "2") (pinfunction "2_2") (pintype "passive"))
      (node (ref "C623") (pin "2") (pinfunction "2_2") (pintype "passive"))
      (node (ref "C624") (pin "2") (pinfunction "2_2") (pintype "passive"))
      (node (ref "C637") (pin "2") (pinfunction "2_2") (pintype "passive"))
      (node (ref "C638") (pin "2") (pinfunction "2_2") (pintype "passive"))
      (node (ref "C639") (pin "2") (pinfunction "2_2") (pintype "passive"))
      (node (ref "C640") (pin "2") (pinfunction "2_2") (pintype "passive"))
      (node (ref "C641") (pin "2") (pinfunction "2_2") (pintype "passive"))
      (node (ref "C652") (pin "2") (pinfunction "2_2") (pintype "passive"))
      (node (ref "C653") (pin "2") (pinfunction "2_2") (pintype "passive"))
      (node (ref "R601") (pin "2") (pinfunction "2_2") (pintype "passive"))
      (node (ref "R605") (pin "2") (pinfunction "2_2") (pintype "passive"))
      (node (ref "U1") (pin "104") (pinfunction "VDDMEM_104") (pintype "passive"))
      (node (ref "U1") (pin "112") (pinfunction "VDDMEM_112") (pintype "passive"))
      (node (ref "U1") (pin "124") (pinfunction "VDDMEM_124") (pintype "passive"))
      (node (ref "U1") (pin "126") (pinfunction "VDDFLASH_126") (pintype "passive"))
      (node (ref "U1") (pin "128") (pinfunction "VDDEXT_128") (pintype "passive"))
      (node (ref "U1") (pin "129") (pinfunction "VDDEXT_129") (pintype "passive"))
      (node (ref "U1") (pin "136") (pinfunction "VDDEXT_136") (pintype "passive"))
      (node (ref "U1") (pin "142") (pinfunction "VDDRTC_142") (pintype "passive"))
      (node (ref "U1") (pin "145") (pinfunction "VDDEXT_145") (pintype "passive"))
      (node (ref "U1") (pin "148") (pinfunction "VDDEXT_148") (pintype "passive"))
      (node (ref "U1") (pin "158") (pinfunction "VDDEXT_158") (pintype "passive"))
      (node (ref "U1") (pin "16") (pinfunction "VDDFLASH_16") (pintype "passive"))
      (node (ref "U1") (pin "17") (pinfunction "VDDFLASH_17") (pintype "passive"))
      (node (ref "U1") (pin "170") (pinfunction "VDDEXT_170") (pintype "passive"))
      (node (ref "U1") (pin "24") (pinfunction "VDDEXT_24") (pintype "passive"))
      (node (ref "U1") (pin "29") (pinfunction "VDDFLASH_29") (pintype "passive"))
      (node (ref "U1") (pin "35") (pinfunction "VDDEXT_35") (pintype "passive"))
      (node (ref "U1") (pin "49") (pinfunction "VDDEXT_49") (pintype "passive"))
      (node (ref "U1") (pin "59") (pinfunction "VDDMEM_59") (pintype "passive"))
      (node (ref "U1") (pin "68") (pinfunction "VDDMEM_68") (pintype "passive"))
      (node (ref "U1") (pin "7") (pinfunction "VDDEXT_7") (pintype "passive"))
      (node (ref "U1") (pin "75") (pinfunction "VDDMEM_75") (pintype "passive"))
      (node (ref "U1") (pin "82") (pinfunction "VDDMEM_82") (pintype "passive"))
      (node (ref "U1") (pin "95") (pinfunction "VDDMEM_95") (pintype "passive"))
      (node (ref "U600") (pin "3") (pinfunction "IN_3") (pintype "passive"))
      (node (ref "U601") (pin "1") (pinfunction "IN_1") (pintype "passive"))
    )
    (net (code "19") (name "VCC5V") (class "Default")
      (node (ref "R608") (pin "2") (pinfunction "2_2") (pintype "passive"))
    )
    (net (code "20") (name "VCC9V") (class "Default")
      (node (ref "C643") (pin "2") (pinfunction "2_2") (pintype "passive"))
      (node (ref "C644") (pin "2") (pinfunction "2_2") (pintype "passive"))
      (node (ref "C648") (pin "2") (pinfunction "2_2") (pintype "passive"))
      (node (ref "C649") (pin "2") (pinfunction "2_2") (pintype "passive"))
      (node (ref "D601") (pin "2") (pinfunction "K_2") (pintype "passive"))
      (node (ref "U602") (pin "7") (pinfunction "VIN_7") (pintype "passive"))
      (node (ref "U603") (pin "7") (pinfunction "VIN_7") (pintype "passive"))
    )
    (net (code "21") (name "unconnected-(U602-ENA-Pad5)") (class "Default")
      (node (ref "U602") (pin "5") (pinfunction "ENA_5") (pintype "passive+no_connect"))
    )
    (net (code "22") (name "unconnected-(U602-NC-Pad2)") (class "Default")
      (node (ref "U602") (pin "2") (pinfunction "NC_2") (pintype "passive+no_connect"))
    )
    (net (code "23") (name "unconnected-(U602-NC-Pad3)") (class "Default")
      (node (ref "U602") (pin "3") (pinfunction "NC_3") (pintype "passive+no_connect"))
    )
    (net (code "24") (name "unconnected-(U603-ENA-Pad5)") (class "Default")
      (node (ref "U603") (pin "5") (pinfunction "ENA_5") (pintype "passive+no_connect"))
    )
    (net (code "25") (name "unconnected-(U603-NC-Pad2)") (class "Default")
      (node (ref "U603") (pin "2") (pinfunction "NC_2") (pintype "passive+no_connect"))
    )
    (net (code "26") (name "unconnected-(U603-NC-Pad3)") (class "Default")
      (node (ref "U603") (pin "3") (pinfunction "NC_3") (pintype "passive+no_connect"))
    )
  )
)
